# 2.net
KiCad netlist of a schematic drawn in Altium Designer
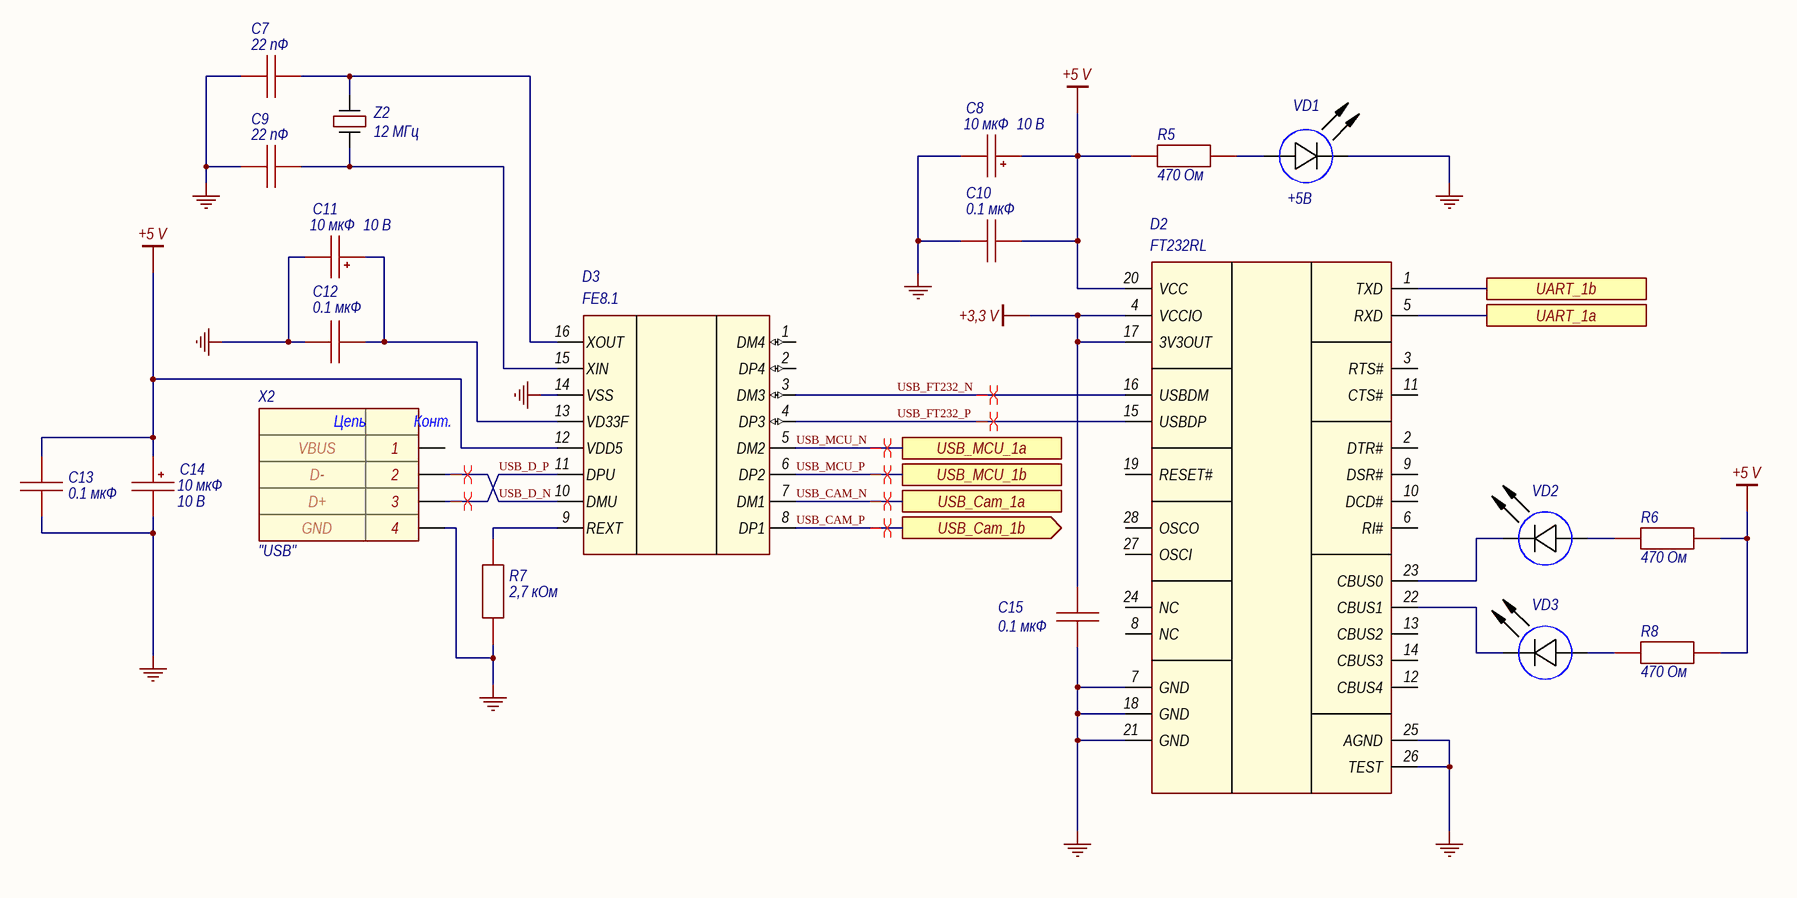
[diagram p0: Лист 2.SchDoc]

(export (version "E")
  (design (tool "Eeschema 10.0.6"))
  (components
    (comp (ref "C7")
      (value "22 пФ")
      (footprint "StandardCase:CAP: 0805")
      (fields
        (field (name "MANUFACTURER") "Yageo")
        (field (name "PARTNUMBER") "CC0805KRX7R7BB104")
        (field (name "VALUEMANUFACTURERPARTNUMBER") "Ceramic capacitor, 22 пФ, X7R, ±10%, 16V, 0805, -55...+125°C")
      )
      (libsource (lib "Capacitor") (part "Ceramic_0805"))
    )
    (comp (ref "C8")
      (value "10 мкФ")
      (footprint "StandardCase:CAP: TANTAL-A")
      (fields
        (field (name "MANUFACTURER") "AVX")
        (field (name "PARTNUMBER") "F930J107KAAAJ6")
        (field (name "VALUEMANUFACTURERPARTNUMBER") "Tantalum capacitor, 10 мкФ, 10 В, ±10%, 2Ohm, case A (3216), -55...+125°C")
        (field (name "VOLTAGE") "10 В")
      )
      (libsource (lib "Capacitor") (part "Tantal_A"))
    )
    (comp (ref "C9")
      (value "22 пФ")
      (footprint "StandardCase:CAP: 0805")
      (fields
        (field (name "MANUFACTURER") "Yageo")
        (field (name "PARTNUMBER") "CC0805KRX7R7BB104")
        (field (name "VALUEMANUFACTURERPARTNUMBER") "Ceramic capacitor, 22 пФ, X7R, ±10%, 16V, 0805, -55...+125°C")
      )
      (libsource (lib "Capacitor") (part "Ceramic_0805"))
    )
    (comp (ref "C10")
      (value "0.1 мкФ")
      (footprint "StandardCase:CAP: 0805")
      (fields
        (field (name "MANUFACTURER") "Yageo")
        (field (name "PARTNUMBER") "CC0805KRX7R7BB104")
        (field (name "VALUEMANUFACTURERPARTNUMBER") "Ceramic capacitor, 0.1 мкФ, X7R, ±10%, 16V, 0805, -55...+125°C")
      )
      (libsource (lib "Capacitor") (part "Ceramic_0805"))
    )
    (comp (ref "C11")
      (value "10 мкФ")
      (footprint "StandardCase:CAP: TANTAL-A")
      (fields
        (field (name "MANUFACTURER") "AVX")
        (field (name "PARTNUMBER") "F930J107KAAAJ6")
        (field (name "VALUEMANUFACTURERPARTNUMBER") "Tantalum capacitor, 10 мкФ, 10 В, ±10%, 2Ohm, case A (3216), -55...+125°C")
        (field (name "VOLTAGE") "10 В")
      )
      (libsource (lib "Capacitor") (part "Tantal_A"))
    )
    (comp (ref "C12")
      (value "0.1 мкФ")
      (footprint "StandardCase:CAP: 0805")
      (fields
        (field (name "MANUFACTURER") "Yageo")
        (field (name "PARTNUMBER") "CC0805KRX7R7BB104")
        (field (name "VALUEMANUFACTURERPARTNUMBER") "Ceramic capacitor, 0.1 мкФ, X7R, ±10%, 16V, 0805, -55...+125°C")
      )
      (libsource (lib "Capacitor") (part "Ceramic_0805"))
    )
    (comp (ref "C13")
      (value "0.1 мкФ")
      (footprint "StandardCase:CAP: 0805")
      (fields
        (field (name "MANUFACTURER") "Yageo")
        (field (name "PARTNUMBER") "CC0805KRX7R7BB104")
        (field (name "VALUEMANUFACTURERPARTNUMBER") "Ceramic capacitor, 0.1 мкФ, X7R, ±10%, 16V, 0805, -55...+125°C")
      )
      (libsource (lib "Capacitor") (part "Ceramic_0805"))
    )
    (comp (ref "C14")
      (value "10 мкФ")
      (footprint "StandardCase:CAP: TANTAL-A")
      (fields
        (field (name "MANUFACTURER") "AVX")
        (field (name "PARTNUMBER") "F930J107KAAAJ6")
        (field (name "VALUEMANUFACTURERPARTNUMBER") "Tantalum capacitor, 10 мкФ, 10 В, ±10%, 2Ohm, case A (3216), -55...+125°C")
        (field (name "VOLTAGE") "10 В")
      )
      (libsource (lib "Capacitor") (part "Tantal_A"))
    )
    (comp (ref "C15")
      (value "0.1 мкФ")
      (footprint "StandardCase:CAP: 0805")
      (fields
        (field (name "MANUFACTURER") "Yageo")
        (field (name "PARTNUMBER") "CC0805KRX7R7BB104")
        (field (name "VALUEMANUFACTURERPARTNUMBER") "Ceramic capacitor, 0.1 мкФ, X7R, ±10%, 16V, 0805, -55...+125°C")
      )
      (libsource (lib "Capacitor") (part "Ceramic_0805"))
    )
    (comp (ref "D2")
      (value "FT232RL")
      (footprint "StandardCase:28-SSOP")
      (description "USB-UART")
      (libsource (lib "IC. Interface") (part "FT232RL"))
    )
    (comp (ref "D3")
      (value "FE8.1")
      (footprint "StandardCase:16-SSOP")
      (libsource (lib "IC. USB Hub") (part "FE8.1"))
    )
    (comp (ref "R5")
      (value "470 Ом")
      (footprint "StandardCase:RES: 0805")
      (fields
        (field (name "MANUFACTURER") "Yageo")
        (field (name "PARTNUMBER") "RC0805JR-07100RL")
        (field (name "VALUEMANUFACTURERPARTNUMBER") "Resistor film, 470 Ом, ±5%, 0805, 0.125W, -55...+125°C")
      )
      (libsource (lib "Resistor") (part "Resistor_0805"))
    )
    (comp (ref "R6")
      (value "470 Ом")
      (footprint "StandardCase:RES: 0805")
      (fields
        (field (name "MANUFACTURER") "Yageo")
        (field (name "PARTNUMBER") "RC0805JR-07100RL")
        (field (name "VALUEMANUFACTURERPARTNUMBER") "Resistor film, 470 Ом, ±5%, 0805, 0.125W, -55...+125°C")
      )
      (libsource (lib "Resistor") (part "Resistor_0805"))
    )
    (comp (ref "R7")
      (value "2,7 кОм")
      (footprint "StandardCase:RES: 0805")
      (fields
        (field (name "MANUFACTURER") "Yageo")
        (field (name "PARTNUMBER") "RC0805JR-07100RL")
        (field (name "VALUEMANUFACTURERPARTNUMBER") "Resistor film, 2,7 кОм, ±5%, 0805, 0.125W, -55...+125°C")
      )
      (libsource (lib "") (part "Resistor_0805_1"))
    )
    (comp (ref "R8")
      (value "470 Ом")
      (footprint "StandardCase:RES: 0805")
      (fields
        (field (name "MANUFACTURER") "Yageo")
        (field (name "PARTNUMBER") "RC0805JR-07100RL")
        (field (name "VALUEMANUFACTURERPARTNUMBER") "Resistor film, 470 Ом, ±5%, 0805, 0.125W, -55...+125°C")
      )
      (libsource (lib "Resistor") (part "Resistor_0805"))
    )
    (comp (ref "VD1")
      (value "+5В")
      (footprint "StandardCase:LED: 0805G")
      (fields (field (name "VALUEMANUFACTURERPARTNUMBER") "LED, *, *, *, -55...+150°C"))
      (libsource (lib "Diode") (part "LED_single"))
    )
    (comp (ref "VD2")
      (value "~")
      (footprint "StandardCase:LED: 0805G")
      (fields (field (name "VALUEMANUFACTURERPARTNUMBER") "LED, *, *, *, -55...+150°C"))
      (libsource (lib "Diode") (part "LED_single"))
    )
    (comp (ref "VD3")
      (value "~")
      (footprint "StandardCase:LED: 0805G")
      (fields (field (name "VALUEMANUFACTURERPARTNUMBER") "LED, *, *, *, -55...+150°C"))
      (libsource (lib "Diode") (part "LED_single"))
    )
    (comp (ref "X2")
      (value "\"USB\"")
      (footprint "CustomCase:CON: USB type B")
      (libsource (lib "Connector") (part "Connector_USB_B"))
    )
    (comp (ref "Z2")
      (value "12 МГц")
      (footprint "CustomCase:OSC: 5032 2 pin")
      (libsource (lib "Oscilator") (part "Crystal_5032_2_pin"))
    )
  )
  (nets
    (net (code "1") (name "+3,3 V") (class "Default")
      (node (ref "C15") (pin "2") (pinfunction "2_2") (pintype "power_in"))
      (node (ref "D2") (pin "17") (pinfunction "3V3OUT_17") (pintype "passive"))
      (node (ref "D2") (pin "4") (pinfunction "VCCIO_4") (pintype "passive"))
    )
    (net (code "2") (name "+5 V") (class "Default")
      (node (ref "C10") (pin "1") (pinfunction "1_1") (pintype "power_in"))
      (node (ref "C13") (pin "2") (pinfunction "2_2") (pintype "power_in"))
      (node (ref "C14") (pin "1") (pinfunction "1_1") (pintype "power_in"))
      (node (ref "C8") (pin "1") (pinfunction "1_1") (pintype "power_in"))
      (node (ref "D2") (pin "20") (pinfunction "VCC_20") (pintype "passive"))
      (node (ref "D3") (pin "12") (pinfunction "VDD5_12") (pintype "passive"))
      (node (ref "R5") (pin "2") (pinfunction "2_2") (pintype "passive"))
      (node (ref "R6") (pin "1") (pinfunction "1_1") (pintype "passive"))
      (node (ref "R8") (pin "1") (pinfunction "1_1") (pintype "passive"))
    )
    (net (code "3") (name "/UART_1a") (class "Default")
      (node (ref "D2") (pin "5") (pinfunction "RXD_5") (pintype "passive"))
    )
    (net (code "4") (name "/UART_1b") (class "Default")
      (node (ref "D2") (pin "1") (pinfunction "TXD_1") (pintype "passive"))
    )
    (net (code "5") (name "/USB_CAM_N") (class "Default")
      (node (ref "D3") (pin "7") (pinfunction "DM1_7") (pintype "passive"))
    )
    (net (code "6") (name "/USB_CAM_P") (class "Default")
      (node (ref "D3") (pin "8") (pinfunction "DP1_8") (pintype "passive"))
    )
    (net (code "7") (name "/USB_D_N") (class "Default")
      (node (ref "D3") (pin "10") (pinfunction "DMU_10") (pintype "passive"))
      (node (ref "X2") (pin "2") (pinfunction "2_2") (pintype "passive"))
    )
    (net (code "8") (name "/USB_D_P") (class "Default")
      (node (ref "D3") (pin "11") (pinfunction "DPU_11") (pintype "passive"))
      (node (ref "X2") (pin "3") (pinfunction "3_3") (pintype "passive"))
    )
    (net (code "9") (name "/USB_FT232_N") (class "Default")
      (node (ref "D2") (pin "16") (pinfunction "USBDM_16") (pintype "passive"))
      (node (ref "D3") (pin "3") (pinfunction "DM3_3") (pintype "bidirectional"))
    )
    (net (code "10") (name "/USB_FT232_P") (class "Default")
      (node (ref "D2") (pin "15") (pinfunction "USBDP_15") (pintype "passive"))
      (node (ref "D3") (pin "4") (pinfunction "DP3_4") (pintype "bidirectional"))
    )
    (net (code "11") (name "/USB_MCU_N") (class "Default")
      (node (ref "D3") (pin "5") (pinfunction "DM2_5") (pintype "passive"))
    )
    (net (code "12") (name "/USB_MCU_P") (class "Default")
      (node (ref "D3") (pin "6") (pinfunction "DP2_6") (pintype "passive"))
    )
    (net (code "13") (name "GND") (class "Default")
      (node (ref "C10") (pin "2") (pinfunction "2_2") (pintype "power_in"))
      (node (ref "C11") (pin "2") (pinfunction "2_2") (pintype "power_in"))
      (node (ref "C12") (pin "2") (pinfunction "2_2") (pintype "power_in"))
      (node (ref "C13") (pin "1") (pinfunction "1_1") (pintype "power_in"))
      (node (ref "C14") (pin "2") (pinfunction "2_2") (pintype "power_in"))
      (node (ref "C15") (pin "1") (pinfunction "1_1") (pintype "power_in"))
      (node (ref "C7") (pin "1") (pinfunction "1_1") (pintype "power_in"))
      (node (ref "C8") (pin "2") (pinfunction "2_2") (pintype "power_in"))
      (node (ref "C9") (pin "1") (pinfunction "1_1") (pintype "power_in"))
      (node (ref "D2") (pin "18") (pinfunction "GND_18") (pintype "passive"))
      (node (ref "D2") (pin "21") (pinfunction "GND_21") (pintype "passive"))
      (node (ref "D2") (pin "25") (pinfunction "AGND_25") (pintype "passive"))
      (node (ref "D2") (pin "26") (pinfunction "TEST_26") (pintype "passive"))
      (node (ref "D2") (pin "7") (pinfunction "GND_7") (pintype "passive"))
      (node (ref "D3") (pin "14") (pinfunction "VSS_14") (pintype "passive"))
      (node (ref "R7") (pin "2") (pinfunction "2_2") (pintype "passive"))
      (node (ref "VD1") (pin "2") (pinfunction "C_2") (pintype "passive"))
      (node (ref "X2") (pin "4") (pinfunction "4_4") (pintype "passive"))
    )
    (net (code "14") (name "Net-(D2-CBUS0)") (class "Default")
      (node (ref "D2") (pin "23") (pinfunction "CBUS0_23") (pintype "passive"))
      (node (ref "VD2") (pin "2") (pinfunction "C_2") (pintype "passive"))
    )
    (net (code "15") (name "Net-(D2-CBUS1)") (class "Default")
      (node (ref "D2") (pin "22") (pinfunction "CBUS1_22") (pintype "passive"))
      (node (ref "VD3") (pin "2") (pinfunction "C_2") (pintype "passive"))
    )
    (net (code "16") (name "Net-(D3-REXT)") (class "Default")
      (node (ref "D3") (pin "9") (pinfunction "REXT_9") (pintype "passive"))
      (node (ref "R7") (pin "1") (pinfunction "1_1") (pintype "passive"))
    )
    (net (code "17") (name "Net-(D3-VD33F)") (class "Default")
      (node (ref "C11") (pin "1") (pinfunction "1_1") (pintype "power_in"))
      (node (ref "C12") (pin "1") (pinfunction "1_1") (pintype "power_in"))
      (node (ref "D3") (pin "13") (pinfunction "VD33F_13") (pintype "passive"))
    )
    (net (code "18") (name "Net-(D3-XIN)") (class "Default")
      (node (ref "C9") (pin "2") (pinfunction "2_2") (pintype "power_in"))
      (node (ref "D3") (pin "15") (pinfunction "XIN_15") (pintype "passive"))
      (node (ref "Z2") (pin "2") (pinfunction "2_2") (pintype "passive"))
    )
    (net (code "19") (name "Net-(D3-XOUT)") (class "Default")
      (node (ref "C7") (pin "2") (pinfunction "2_2") (pintype "power_in"))
      (node (ref "D3") (pin "16") (pinfunction "XOUT_16") (pintype "passive"))
      (node (ref "Z2") (pin "1") (pinfunction "1_1") (pintype "passive"))
    )
    (net (code "20") (name "Net-(VD1-A)") (class "Default")
      (node (ref "R5") (pin "1") (pinfunction "1_1") (pintype "passive"))
      (node (ref "VD1") (pin "1") (pinfunction "A_1") (pintype "passive"))
    )
    (net (code "21") (name "Net-(VD2-A)") (class "Default")
      (node (ref "R6") (pin "2") (pinfunction "2_2") (pintype "passive"))
      (node (ref "VD2") (pin "1") (pinfunction "A_1") (pintype "passive"))
    )
    (net (code "22") (name "Net-(VD3-A)") (class "Default")
      (node (ref "R8") (pin "2") (pinfunction "2_2") (pintype "passive"))
      (node (ref "VD3") (pin "1") (pinfunction "A_1") (pintype "passive"))
    )
    (net (code "23") (name "unconnected-(D2-CBUS2-Pad13)") (class "Default")
      (node (ref "D2") (pin "13") (pinfunction "CBUS2_13") (pintype "passive"))
    )
    (net (code "24") (name "unconnected-(D2-CBUS3-Pad14)") (class "Default")
      (node (ref "D2") (pin "14") (pinfunction "CBUS3_14") (pintype "passive"))
    )
    (net (code "25") (name "unconnected-(D2-CBUS4-Pad12)") (class "Default")
      (node (ref "D2") (pin "12") (pinfunction "CBUS4_12") (pintype "passive"))
    )
    (net (code "26") (name "unconnected-(D2-CTS#-Pad11)") (class "Default")
      (node (ref "D2") (pin "11") (pinfunction "CTS#_11") (pintype "passive"))
    )
    (net (code "27") (name "unconnected-(D2-DCD#-Pad10)") (class "Default")
      (node (ref "D2") (pin "10") (pinfunction "DCD#_10") (pintype "passive"))
    )
    (net (code "28") (name "unconnected-(D2-DSR#-Pad9)") (class "Default")
      (node (ref "D2") (pin "9") (pinfunction "DSR#_9") (pintype "passive"))
    )
    (net (code "29") (name "unconnected-(D2-DTR#-Pad2)") (class "Default")
      (node (ref "D2") (pin "2") (pinfunction "DTR#_2") (pintype "passive"))
    )
    (net (code "30") (name "unconnected-(D2-NC-Pad8)") (class "Default")
      (node (ref "D2") (pin "8") (pinfunction "NC_8") (pintype "passive"))
    )
    (net (code "31") (name "unconnected-(D2-NC-Pad24)") (class "Default")
      (node (ref "D2") (pin "24") (pinfunction "NC_24") (pintype "passive"))
    )
    (net (code "32") (name "unconnected-(D2-OSCI-Pad27)") (class "Default")
      (node (ref "D2") (pin "27") (pinfunction "OSCI_27") (pintype "passive"))
    )
    (net (code "33") (name "unconnected-(D2-OSCO-Pad28)") (class "Default")
      (node (ref "D2") (pin "28") (pinfunction "OSCO_28") (pintype "passive"))
    )
    (net (code "34") (name "unconnected-(D2-RESET#-Pad19)") (class "Default")
      (node (ref "D2") (pin "19") (pinfunction "RESET#_19") (pintype "passive"))
    )
    (net (code "35") (name "unconnected-(D2-RI#-Pad6)") (class "Default")
      (node (ref "D2") (pin "6") (pinfunction "RI#_6") (pintype "passive"))
    )
    (net (code "36") (name "unconnected-(D2-RTS#-Pad3)") (class "Default")
      (node (ref "D2") (pin "3") (pinfunction "RTS#_3") (pintype "passive"))
    )
    (net (code "37") (name "unconnected-(D3-DM4-Pad1)") (class "Default")
      (node (ref "D3") (pin "1") (pinfunction "DM4_1") (pintype "bidirectional"))
    )
    (net (code "38") (name "unconnected-(D3-DP4-Pad2)") (class "Default")
      (node (ref "D3") (pin "2") (pinfunction "DP4_2") (pintype "bidirectional"))
    )
    (net (code "39") (name "unconnected-(X2-Pad1)") (class "Default")
      (node (ref "X2") (pin "1") (pinfunction "1_1") (pintype "passive"))
    )
  )
)
